# I2C_CH3.net
KiCad netlist of a schematic drawn in Altium Designer
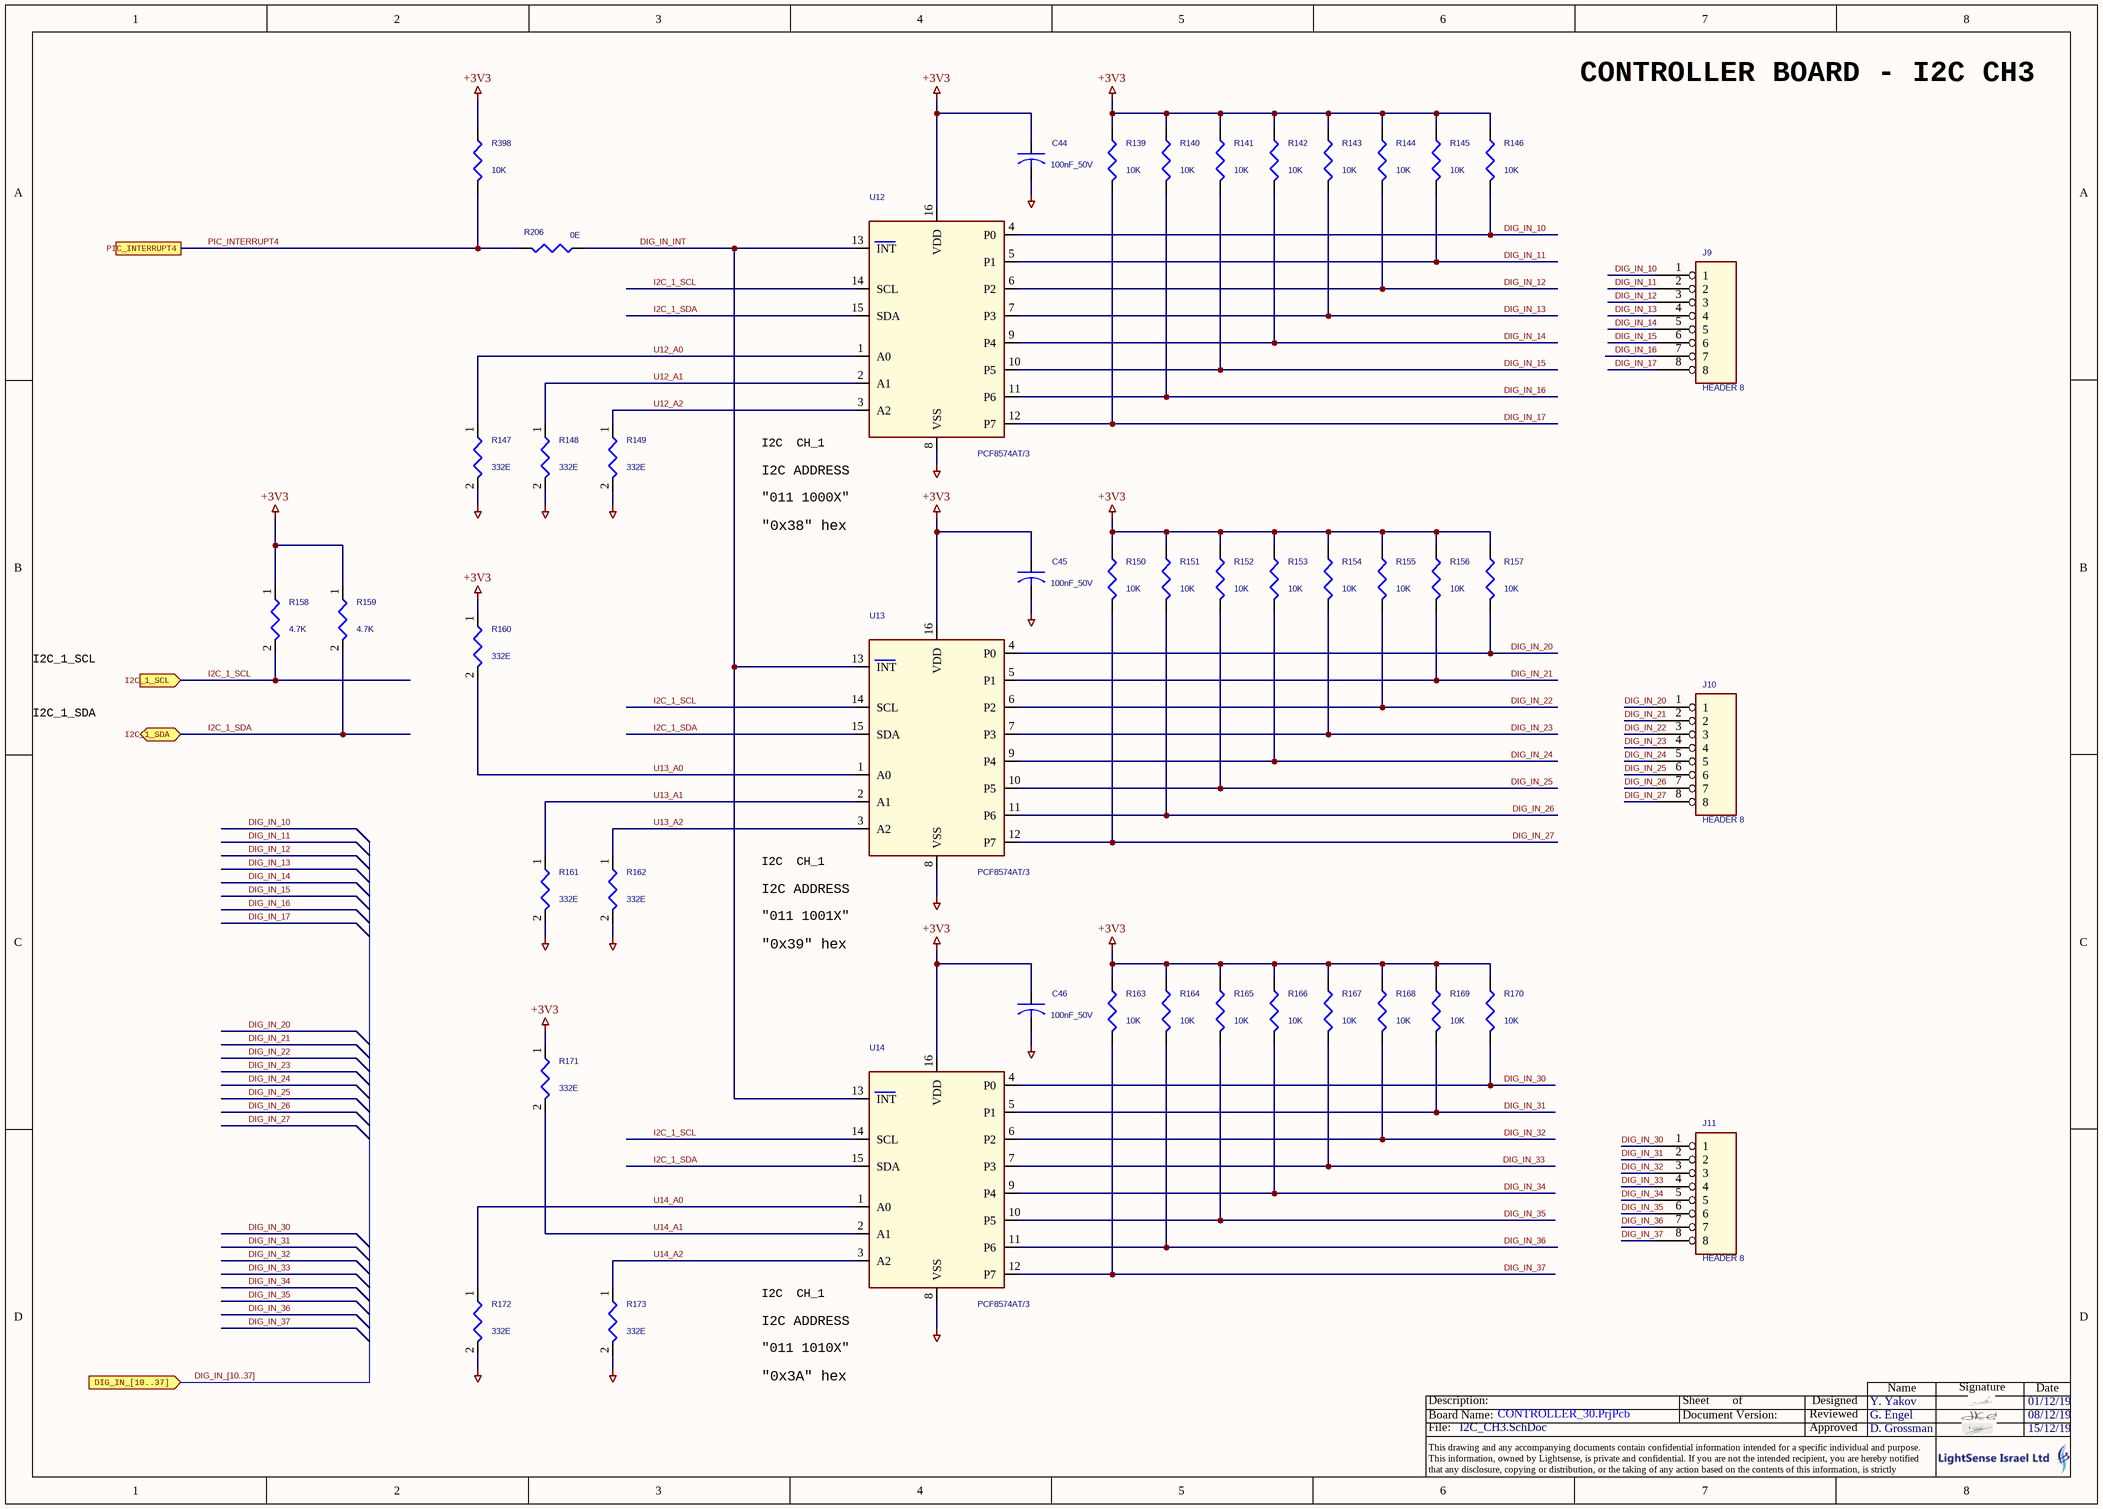
[diagram p0: I2C_CH3.SchDoc]

(export (version "E")
  (design (tool "Eeschema 10.0.6"))
  (components
    (comp (ref "C44")
      (value "100nF_50V")
      (footprint "0603")
      (description "CAP_SMT_0603_50V_X7R_10%")
      (fields (field (name "MFG") "KEMET"))
      (libsource (lib "*") (part "C"))
    )
    (comp (ref "C45")
      (value "100nF_50V")
      (footprint "0603")
      (description "CAP_SMT_0603_50V_X7R_10%")
      (fields (field (name "MFG") "KEMET"))
      (libsource (lib "*") (part "C"))
    )
    (comp (ref "C46")
      (value "100nF_50V")
      (footprint "0603")
      (description "CAP_SMT_0603_50V_X7R_10%")
      (fields (field (name "MFG") "KEMET"))
      (libsource (lib "*") (part "C"))
    )
    (comp (ref "J9") (value "HEADER 8") (footprint "TH_8PIN_100mil") (libsource (lib "*") (part "HEADER 8")))
    (comp (ref "J10") (value "HEADER 8") (footprint "TH_8PIN_100mil") (libsource (lib "*") (part "HEADER 8")))
    (comp (ref "J11") (value "HEADER 8") (footprint "TH_8PIN_100mil") (libsource (lib "*") (part "HEADER 8")))
    (comp (ref "R139")
      (value "10K")
      (footprint "0603")
      (fields (field (name "MFG") "YAGEO"))
      (libsource (lib "*") (part "R_Dup1"))
    )
    (comp (ref "R140")
      (value "10K")
      (footprint "0603")
      (fields (field (name "MFG") "YAGEO"))
      (libsource (lib "*") (part "R_Dup1"))
    )
    (comp (ref "R141")
      (value "10K")
      (footprint "0603")
      (fields (field (name "MFG") "YAGEO"))
      (libsource (lib "*") (part "R_Dup1"))
    )
    (comp (ref "R142")
      (value "10K")
      (footprint "0603")
      (fields (field (name "MFG") "YAGEO"))
      (libsource (lib "*") (part "R_Dup1"))
    )
    (comp (ref "R143")
      (value "10K")
      (footprint "0603")
      (fields (field (name "MFG") "YAGEO"))
      (libsource (lib "*") (part "R_Dup1"))
    )
    (comp (ref "R144")
      (value "10K")
      (footprint "0603")
      (fields (field (name "MFG") "YAGEO"))
      (libsource (lib "*") (part "R_Dup1"))
    )
    (comp (ref "R145")
      (value "10K")
      (footprint "0603")
      (fields (field (name "MFG") "YAGEO"))
      (libsource (lib "*") (part "R_Dup1"))
    )
    (comp (ref "R146")
      (value "10K")
      (footprint "0603")
      (fields (field (name "MFG") "YAGEO"))
      (libsource (lib "*") (part "R_Dup1"))
    )
    (comp (ref "R147")
      (value "332E")
      (footprint "R0603")
      (fields (field (name "MFG") "YAGEO"))
      (libsource (lib "*") (part "R"))
    )
    (comp (ref "R148")
      (value "332E")
      (footprint "R0603")
      (fields (field (name "MFG") "YAGEO"))
      (libsource (lib "*") (part "R"))
    )
    (comp (ref "R149")
      (value "332E")
      (footprint "R0603")
      (fields (field (name "MFG") "YAGEO"))
      (libsource (lib "*") (part "R"))
    )
    (comp (ref "R150")
      (value "10K")
      (footprint "0603")
      (fields (field (name "MFG") "YAGEO"))
      (libsource (lib "*") (part "R_Dup1"))
    )
    (comp (ref "R151")
      (value "10K")
      (footprint "0603")
      (fields (field (name "MFG") "YAGEO"))
      (libsource (lib "*") (part "R_Dup1"))
    )
    (comp (ref "R152")
      (value "10K")
      (footprint "0603")
      (fields (field (name "MFG") "YAGEO"))
      (libsource (lib "*") (part "R_Dup1"))
    )
    (comp (ref "R153")
      (value "10K")
      (footprint "0603")
      (fields (field (name "MFG") "YAGEO"))
      (libsource (lib "*") (part "R_Dup1"))
    )
    (comp (ref "R154")
      (value "10K")
      (footprint "0603")
      (fields (field (name "MFG") "YAGEO"))
      (libsource (lib "*") (part "R_Dup1"))
    )
    (comp (ref "R155")
      (value "10K")
      (footprint "0603")
      (fields (field (name "MFG") "YAGEO"))
      (libsource (lib "*") (part "R_Dup1"))
    )
    (comp (ref "R156")
      (value "10K")
      (footprint "0603")
      (fields (field (name "MFG") "YAGEO"))
      (libsource (lib "*") (part "R_Dup1"))
    )
    (comp (ref "R157")
      (value "10K")
      (footprint "0603")
      (fields (field (name "MFG") "YAGEO"))
      (libsource (lib "*") (part "R_Dup1"))
    )
    (comp (ref "R158")
      (value "4.7K")
      (footprint "R0603")
      (fields (field (name "MFG") "YAGEO"))
      (libsource (lib "*") (part "R"))
    )
    (comp (ref "R159")
      (value "4.7K")
      (footprint "R0603")
      (fields (field (name "MFG") "YAGEO"))
      (libsource (lib "*") (part "R"))
    )
    (comp (ref "R160")
      (value "332E")
      (footprint "R0603")
      (fields (field (name "MFG") "YAGEO"))
      (libsource (lib "*") (part "R"))
    )
    (comp (ref "R161")
      (value "332E")
      (footprint "R0603")
      (fields (field (name "MFG") "YAGEO"))
      (libsource (lib "*") (part "R"))
    )
    (comp (ref "R162")
      (value "332E")
      (footprint "R0603")
      (fields (field (name "MFG") "YAGEO"))
      (libsource (lib "*") (part "R"))
    )
    (comp (ref "R163")
      (value "10K")
      (footprint "0603")
      (fields (field (name "MFG") "YAGEO"))
      (libsource (lib "*") (part "R_Dup1"))
    )
    (comp (ref "R164")
      (value "10K")
      (footprint "0603")
      (fields (field (name "MFG") "YAGEO"))
      (libsource (lib "*") (part "R_Dup1"))
    )
    (comp (ref "R165")
      (value "10K")
      (footprint "0603")
      (fields (field (name "MFG") "YAGEO"))
      (libsource (lib "*") (part "R_Dup1"))
    )
    (comp (ref "R166")
      (value "10K")
      (footprint "0603")
      (fields (field (name "MFG") "YAGEO"))
      (libsource (lib "*") (part "R_Dup1"))
    )
    (comp (ref "R167")
      (value "10K")
      (footprint "0603")
      (fields (field (name "MFG") "YAGEO"))
      (libsource (lib "*") (part "R_Dup1"))
    )
    (comp (ref "R168")
      (value "10K")
      (footprint "0603")
      (fields (field (name "MFG") "YAGEO"))
      (libsource (lib "*") (part "R_Dup1"))
    )
    (comp (ref "R169")
      (value "10K")
      (footprint "0603")
      (fields (field (name "MFG") "YAGEO"))
      (libsource (lib "*") (part "R_Dup1"))
    )
    (comp (ref "R170")
      (value "10K")
      (footprint "0603")
      (fields (field (name "MFG") "YAGEO"))
      (libsource (lib "*") (part "R_Dup1"))
    )
    (comp (ref "R171")
      (value "332E")
      (footprint "R0603")
      (fields (field (name "MFG") "YAGEO"))
      (libsource (lib "*") (part "R"))
    )
    (comp (ref "R172")
      (value "332E")
      (footprint "R0603")
      (fields (field (name "MFG") "YAGEO"))
      (libsource (lib "*") (part "R"))
    )
    (comp (ref "R173")
      (value "332E")
      (footprint "R0603")
      (fields (field (name "MFG") "YAGEO"))
      (libsource (lib "*") (part "R"))
    )
    (comp (ref "R206")
      (value "0E")
      (footprint "0805R")
      (fields (field (name "MFG") "YAGEO"))
      (libsource (lib "CONTROLLER_30_Library") (part "R_Dup1"))
    )
    (comp (ref "R398")
      (value "10K")
      (footprint "0603")
      (fields (field (name "MFG") "YAGEO"))
      (libsource (lib "*") (part "R_Dup1"))
    )
    (comp (ref "U12")
      (value "PCF8574AT/3")
      (footprint "SO_16")
      (description "PORT I2C, 8Bit, SO_16")
      (fields (field (name "MFG") "NXP"))
      (libsource (lib "*") (part "PCF8574_0"))
    )
    (comp (ref "U13")
      (value "PCF8574AT/3")
      (footprint "SO_16")
      (description "PORT I2C, 8Bit, SO_16")
      (fields (field (name "MFG") "NXP"))
      (libsource (lib "*") (part "PCF8574_0"))
    )
    (comp (ref "U14")
      (value "PCF8574AT/3")
      (footprint "SO_16")
      (description "PORT I2C, 8Bit, SO16")
      (fields (field (name "MFG") "NXP"))
      (libsource (lib "*") (part "PCF8574_0"))
    )
  )
  (nets
    (net (code "5") (name "+3V3") (class "Default")
      (node (ref "C44") (pin "1") (pinfunction "1_1") (pintype "passive"))
      (node (ref "C45") (pin "1") (pinfunction "1_1") (pintype "passive"))
      (node (ref "C46") (pin "1") (pinfunction "1_1") (pintype "passive"))
      (node (ref "R139") (pin "1") (pinfunction "1_1") (pintype "passive"))
      (node (ref "R140") (pin "1") (pinfunction "1_1") (pintype "passive"))
      (node (ref "R141") (pin "1") (pinfunction "1_1") (pintype "passive"))
      (node (ref "R142") (pin "1") (pinfunction "1_1") (pintype "passive"))
      (node (ref "R143") (pin "1") (pinfunction "1_1") (pintype "passive"))
      (node (ref "R144") (pin "1") (pinfunction "1_1") (pintype "passive"))
      (node (ref "R145") (pin "1") (pinfunction "1_1") (pintype "passive"))
      (node (ref "R146") (pin "1") (pinfunction "1_1") (pintype "passive"))
      (node (ref "R150") (pin "1") (pinfunction "1_1") (pintype "passive"))
      (node (ref "R151") (pin "1") (pinfunction "1_1") (pintype "passive"))
      (node (ref "R152") (pin "1") (pinfunction "1_1") (pintype "passive"))
      (node (ref "R153") (pin "1") (pinfunction "1_1") (pintype "passive"))
      (node (ref "R154") (pin "1") (pinfunction "1_1") (pintype "passive"))
      (node (ref "R155") (pin "1") (pinfunction "1_1") (pintype "passive"))
      (node (ref "R156") (pin "1") (pinfunction "1_1") (pintype "passive"))
      (node (ref "R157") (pin "1") (pinfunction "1_1") (pintype "passive"))
      (node (ref "R158") (pin "1") (pinfunction "1_1") (pintype "passive"))
      (node (ref "R159") (pin "1") (pinfunction "1_1") (pintype "passive"))
      (node (ref "R160") (pin "1") (pinfunction "1_1") (pintype "passive"))
      (node (ref "R163") (pin "1") (pinfunction "1_1") (pintype "passive"))
      (node (ref "R164") (pin "1") (pinfunction "1_1") (pintype "passive"))
      (node (ref "R165") (pin "1") (pinfunction "1_1") (pintype "passive"))
      (node (ref "R166") (pin "1") (pinfunction "1_1") (pintype "passive"))
      (node (ref "R167") (pin "1") (pinfunction "1_1") (pintype "passive"))
      (node (ref "R168") (pin "1") (pinfunction "1_1") (pintype "passive"))
      (node (ref "R169") (pin "1") (pinfunction "1_1") (pintype "passive"))
      (node (ref "R170") (pin "1") (pinfunction "1_1") (pintype "passive"))
      (node (ref "R171") (pin "1") (pinfunction "1_1") (pintype "passive"))
      (node (ref "R398") (pin "1") (pinfunction "1_1") (pintype "passive"))
      (node (ref "U12") (pin "16") (pinfunction "VDD_16") (pintype "passive"))
      (node (ref "U13") (pin "16") (pinfunction "VDD_16") (pintype "passive"))
      (node (ref "U14") (pin "16") (pinfunction "VDD_16") (pintype "passive"))
    )
    (net (code "6") (name "/DIG_IN_10") (class "Default")
      (node (ref "J9") (pin "1") (pinfunction "1_1") (pintype "passive"))
      (node (ref "R146") (pin "2") (pinfunction "2_2") (pintype "passive"))
      (node (ref "U12") (pin "4") (pinfunction "P0_4") (pintype "passive"))
    )
    (net (code "7") (name "/DIG_IN_11") (class "Default")
      (node (ref "J9") (pin "2") (pinfunction "2_2") (pintype "passive"))
      (node (ref "R145") (pin "2") (pinfunction "2_2") (pintype "passive"))
      (node (ref "U12") (pin "5") (pinfunction "P1_5") (pintype "passive"))
    )
    (net (code "8") (name "/DIG_IN_12") (class "Default")
      (node (ref "J9") (pin "3") (pinfunction "3_3") (pintype "passive"))
      (node (ref "R144") (pin "2") (pinfunction "2_2") (pintype "passive"))
      (node (ref "U12") (pin "6") (pinfunction "P2_6") (pintype "passive"))
    )
    (net (code "9") (name "/DIG_IN_13") (class "Default")
      (node (ref "J9") (pin "4") (pinfunction "4_4") (pintype "passive"))
      (node (ref "R143") (pin "2") (pinfunction "2_2") (pintype "passive"))
      (node (ref "U12") (pin "7") (pinfunction "P3_7") (pintype "passive"))
    )
    (net (code "10") (name "/DIG_IN_14") (class "Default")
      (node (ref "J9") (pin "5") (pinfunction "5_5") (pintype "passive"))
      (node (ref "R142") (pin "2") (pinfunction "2_2") (pintype "passive"))
      (node (ref "U12") (pin "9") (pinfunction "P4_9") (pintype "passive"))
    )
    (net (code "11") (name "/DIG_IN_15") (class "Default")
      (node (ref "J9") (pin "6") (pinfunction "6_6") (pintype "passive"))
      (node (ref "R141") (pin "2") (pinfunction "2_2") (pintype "passive"))
      (node (ref "U12") (pin "10") (pinfunction "P5_10") (pintype "passive"))
    )
    (net (code "12") (name "/DIG_IN_16") (class "Default")
      (node (ref "J9") (pin "7") (pinfunction "7_7") (pintype "passive"))
      (node (ref "R140") (pin "2") (pinfunction "2_2") (pintype "passive"))
      (node (ref "U12") (pin "11") (pinfunction "P6_11") (pintype "passive"))
    )
    (net (code "13") (name "/DIG_IN_17") (class "Default")
      (node (ref "J9") (pin "8") (pinfunction "8_8") (pintype "passive"))
      (node (ref "R139") (pin "2") (pinfunction "2_2") (pintype "passive"))
      (node (ref "U12") (pin "12") (pinfunction "P7_12") (pintype "passive"))
    )
    (net (code "14") (name "/DIG_IN_20") (class "Default")
      (node (ref "J10") (pin "1") (pinfunction "1_1") (pintype "passive"))
      (node (ref "R157") (pin "2") (pinfunction "2_2") (pintype "passive"))
      (node (ref "U13") (pin "4") (pinfunction "P0_4") (pintype "passive"))
    )
    (net (code "15") (name "/DIG_IN_21") (class "Default")
      (node (ref "J10") (pin "2") (pinfunction "2_2") (pintype "passive"))
      (node (ref "R156") (pin "2") (pinfunction "2_2") (pintype "passive"))
      (node (ref "U13") (pin "5") (pinfunction "P1_5") (pintype "passive"))
    )
    (net (code "16") (name "/DIG_IN_22") (class "Default")
      (node (ref "J10") (pin "3") (pinfunction "3_3") (pintype "passive"))
      (node (ref "R155") (pin "2") (pinfunction "2_2") (pintype "passive"))
      (node (ref "U13") (pin "6") (pinfunction "P2_6") (pintype "passive"))
    )
    (net (code "17") (name "/DIG_IN_23") (class "Default")
      (node (ref "J10") (pin "4") (pinfunction "4_4") (pintype "passive"))
      (node (ref "R154") (pin "2") (pinfunction "2_2") (pintype "passive"))
      (node (ref "U13") (pin "7") (pinfunction "P3_7") (pintype "passive"))
    )
    (net (code "18") (name "/DIG_IN_24") (class "Default")
      (node (ref "J10") (pin "5") (pinfunction "5_5") (pintype "passive"))
      (node (ref "R153") (pin "2") (pinfunction "2_2") (pintype "passive"))
      (node (ref "U13") (pin "9") (pinfunction "P4_9") (pintype "passive"))
    )
    (net (code "19") (name "/DIG_IN_25") (class "Default")
      (node (ref "J10") (pin "6") (pinfunction "6_6") (pintype "passive"))
      (node (ref "R152") (pin "2") (pinfunction "2_2") (pintype "passive"))
      (node (ref "U13") (pin "10") (pinfunction "P5_10") (pintype "passive"))
    )
    (net (code "20") (name "/DIG_IN_26") (class "Default")
      (node (ref "J10") (pin "7") (pinfunction "7_7") (pintype "passive"))
      (node (ref "R151") (pin "2") (pinfunction "2_2") (pintype "passive"))
      (node (ref "U13") (pin "11") (pinfunction "P6_11") (pintype "passive"))
    )
    (net (code "21") (name "/DIG_IN_27") (class "Default")
      (node (ref "J10") (pin "8") (pinfunction "8_8") (pintype "passive"))
      (node (ref "R150") (pin "2") (pinfunction "2_2") (pintype "passive"))
      (node (ref "U13") (pin "12") (pinfunction "P7_12") (pintype "passive"))
    )
    (net (code "22") (name "/DIG_IN_30") (class "Default")
      (node (ref "J11") (pin "1") (pinfunction "1_1") (pintype "passive"))
      (node (ref "R170") (pin "2") (pinfunction "2_2") (pintype "passive"))
      (node (ref "U14") (pin "4") (pinfunction "P0_4") (pintype "passive"))
    )
    (net (code "23") (name "/DIG_IN_31") (class "Default")
      (node (ref "J11") (pin "2") (pinfunction "2_2") (pintype "passive"))
      (node (ref "R169") (pin "2") (pinfunction "2_2") (pintype "passive"))
      (node (ref "U14") (pin "5") (pinfunction "P1_5") (pintype "passive"))
    )
    (net (code "24") (name "/DIG_IN_32") (class "Default")
      (node (ref "J11") (pin "3") (pinfunction "3_3") (pintype "passive"))
      (node (ref "R168") (pin "2") (pinfunction "2_2") (pintype "passive"))
      (node (ref "U14") (pin "6") (pinfunction "P2_6") (pintype "passive"))
    )
    (net (code "25") (name "/DIG_IN_33") (class "Default")
      (node (ref "J11") (pin "4") (pinfunction "4_4") (pintype "passive"))
      (node (ref "R167") (pin "2") (pinfunction "2_2") (pintype "passive"))
      (node (ref "U14") (pin "7") (pinfunction "P3_7") (pintype "passive"))
    )
    (net (code "26") (name "/DIG_IN_34") (class "Default")
      (node (ref "J11") (pin "5") (pinfunction "5_5") (pintype "passive"))
      (node (ref "R166") (pin "2") (pinfunction "2_2") (pintype "passive"))
      (node (ref "U14") (pin "9") (pinfunction "P4_9") (pintype "passive"))
    )
    (net (code "27") (name "/DIG_IN_35") (class "Default")
      (node (ref "J11") (pin "6") (pinfunction "6_6") (pintype "passive"))
      (node (ref "R165") (pin "2") (pinfunction "2_2") (pintype "passive"))
      (node (ref "U14") (pin "10") (pinfunction "P5_10") (pintype "passive"))
    )
    (net (code "28") (name "/DIG_IN_36") (class "Default")
      (node (ref "J11") (pin "7") (pinfunction "7_7") (pintype "passive"))
      (node (ref "R164") (pin "2") (pinfunction "2_2") (pintype "passive"))
      (node (ref "U14") (pin "11") (pinfunction "P6_11") (pintype "passive"))
    )
    (net (code "29") (name "/DIG_IN_37") (class "Default")
      (node (ref "J11") (pin "8") (pinfunction "8_8") (pintype "passive"))
      (node (ref "R163") (pin "2") (pinfunction "2_2") (pintype "passive"))
      (node (ref "U14") (pin "12") (pinfunction "P7_12") (pintype "passive"))
    )
    (net (code "30") (name "/DIG_IN_INT") (class "Default")
      (node (ref "R206") (pin "1") (pinfunction "1_1") (pintype "passive"))
      (node (ref "U12") (pin "13") (pinfunction "INT_13") (pintype "passive"))
      (node (ref "U13") (pin "13") (pinfunction "INT_13") (pintype "passive"))
      (node (ref "U14") (pin "13") (pinfunction "INT_13") (pintype "passive"))
    )
    (net (code "32") (name "/I2C_1_SCL") (class "Default")
      (node (ref "R158") (pin "2") (pinfunction "2_2") (pintype "passive"))
      (node (ref "U12") (pin "14") (pinfunction "SCL_14") (pintype "passive"))
      (node (ref "U13") (pin "14") (pinfunction "SCL_14") (pintype "passive"))
      (node (ref "U14") (pin "14") (pinfunction "SCL_14") (pintype "passive"))
    )
    (net (code "33") (name "/I2C_1_SDA") (class "Default")
      (node (ref "R159") (pin "2") (pinfunction "2_2") (pintype "passive"))
      (node (ref "U12") (pin "15") (pinfunction "SDA_15") (pintype "passive"))
      (node (ref "U13") (pin "15") (pinfunction "SDA_15") (pintype "passive"))
      (node (ref "U14") (pin "15") (pinfunction "SDA_15") (pintype "passive"))
    )
    (net (code "34") (name "/PIC_INTERRUPT4") (class "Default")
      (node (ref "R206") (pin "2") (pinfunction "2_2") (pintype "passive"))
      (node (ref "R398") (pin "2") (pinfunction "2_2") (pintype "passive"))
    )
    (net (code "35") (name "/U12_A0") (class "Default")
      (node (ref "R147") (pin "1") (pinfunction "1_1") (pintype "passive"))
      (node (ref "U12") (pin "1") (pinfunction "A0_1") (pintype "passive"))
    )
    (net (code "36") (name "/U12_A1") (class "Default")
      (node (ref "R148") (pin "1") (pinfunction "1_1") (pintype "passive"))
      (node (ref "U12") (pin "2") (pinfunction "A1_2") (pintype "passive"))
    )
    (net (code "37") (name "/U12_A2") (class "Default")
      (node (ref "R149") (pin "1") (pinfunction "1_1") (pintype "passive"))
      (node (ref "U12") (pin "3") (pinfunction "A2_3") (pintype "passive"))
    )
    (net (code "38") (name "/U13_A0") (class "Default")
      (node (ref "R160") (pin "2") (pinfunction "2_2") (pintype "passive"))
      (node (ref "U13") (pin "1") (pinfunction "A0_1") (pintype "passive"))
    )
    (net (code "39") (name "/U13_A1") (class "Default")
      (node (ref "R161") (pin "1") (pinfunction "1_1") (pintype "passive"))
      (node (ref "U13") (pin "2") (pinfunction "A1_2") (pintype "passive"))
    )
    (net (code "40") (name "/U13_A2") (class "Default")
      (node (ref "R162") (pin "1") (pinfunction "1_1") (pintype "passive"))
      (node (ref "U13") (pin "3") (pinfunction "A2_3") (pintype "passive"))
    )
    (net (code "41") (name "/U14_A0") (class "Default")
      (node (ref "R172") (pin "1") (pinfunction "1_1") (pintype "passive"))
      (node (ref "U14") (pin "1") (pinfunction "A0_1") (pintype "passive"))
    )
    (net (code "42") (name "/U14_A1") (class "Default")
      (node (ref "R171") (pin "2") (pinfunction "2_2") (pintype "passive"))
      (node (ref "U14") (pin "2") (pinfunction "A1_2") (pintype "passive"))
    )
    (net (code "43") (name "/U14_A2") (class "Default")
      (node (ref "R173") (pin "1") (pinfunction "1_1") (pintype "passive"))
      (node (ref "U14") (pin "3") (pinfunction "A2_3") (pintype "passive"))
    )
    (net (code "44") (name "GND_CPU") (class "Default")
      (node (ref "C44") (pin "2") (pinfunction "2_2") (pintype "passive"))
      (node (ref "C45") (pin "2") (pinfunction "2_2") (pintype "passive"))
      (node (ref "C46") (pin "2") (pinfunction "2_2") (pintype "passive"))
      (node (ref "R147") (pin "2") (pinfunction "2_2") (pintype "passive"))
      (node (ref "R148") (pin "2") (pinfunction "2_2") (pintype "passive"))
      (node (ref "R149") (pin "2") (pinfunction "2_2") (pintype "passive"))
      (node (ref "R161") (pin "2") (pinfunction "2_2") (pintype "passive"))
      (node (ref "R162") (pin "2") (pinfunction "2_2") (pintype "passive"))
      (node (ref "R172") (pin "2") (pinfunction "2_2") (pintype "passive"))
      (node (ref "R173") (pin "2") (pinfunction "2_2") (pintype "passive"))
      (node (ref "U12") (pin "8") (pinfunction "VSS_8") (pintype "passive"))
      (node (ref "U13") (pin "8") (pinfunction "VSS_8") (pintype "passive"))
      (node (ref "U14") (pin "8") (pinfunction "VSS_8") (pintype "passive"))
    )
  )
)
